# Sheet1.net
KiCad netlist of a schematic drawn in Altium Designer
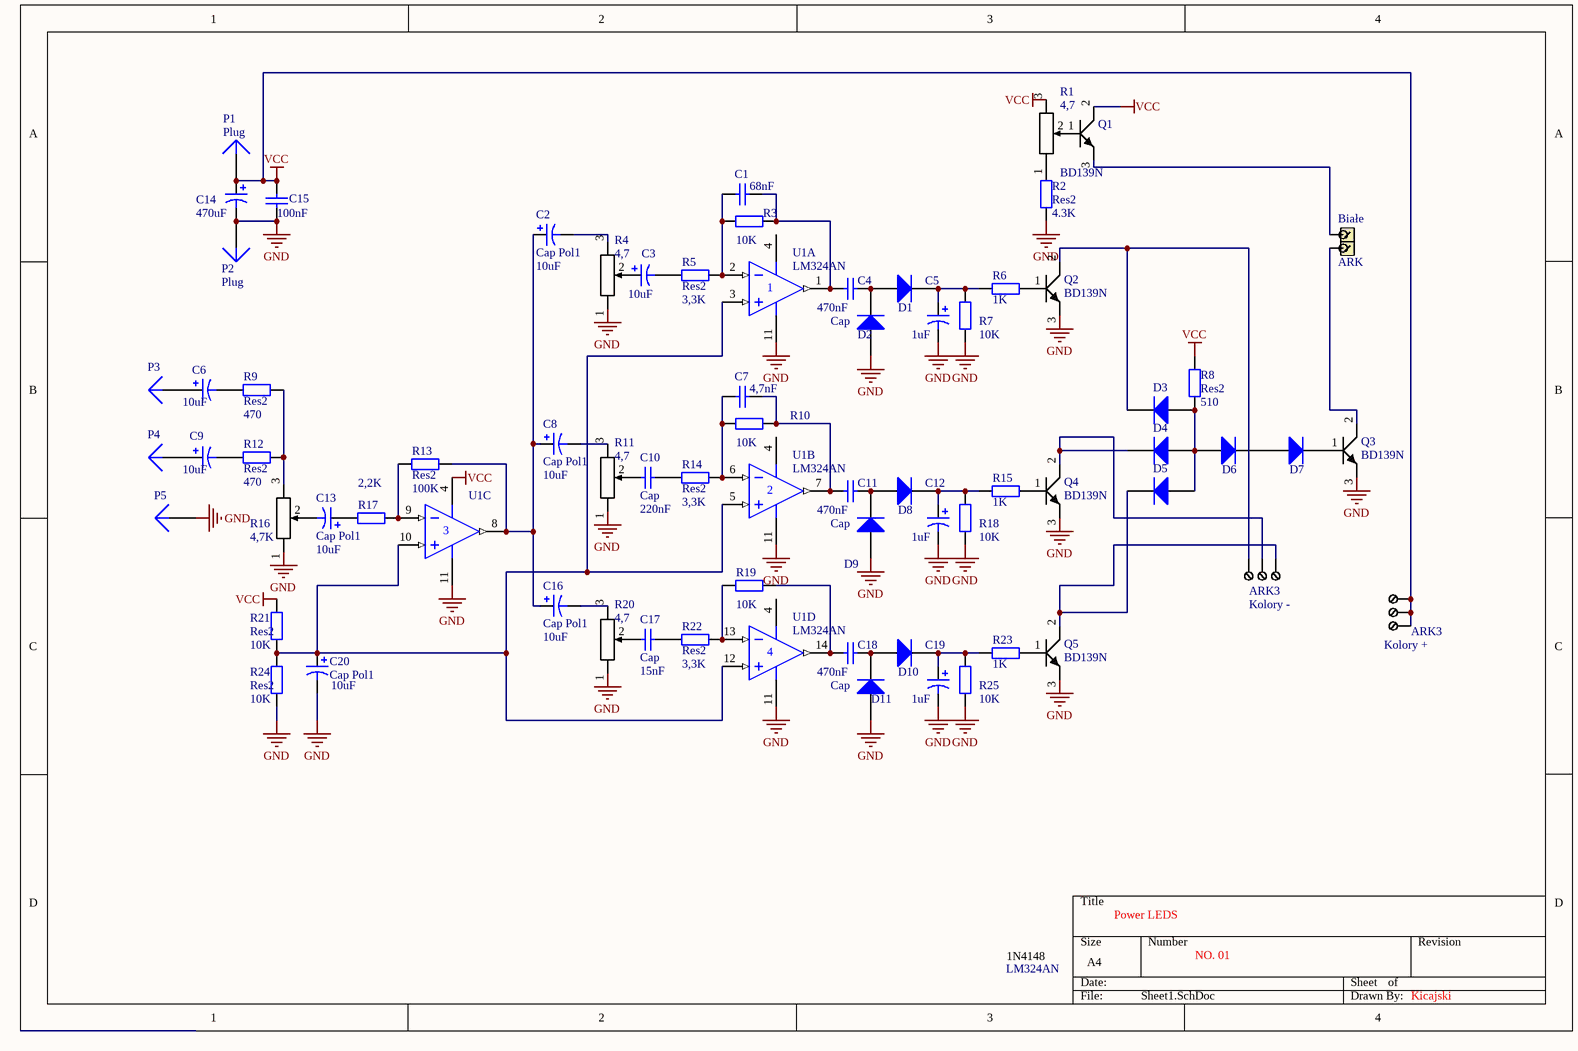
[diagram p0: Sheet1.SchDoc]

(export (version "E")
  (design (tool "Eeschema 10.0.6"))
  (components
    (comp (ref "Białe") (value "ARK") (footprint "ARK2") (libsource (lib "MOJASIM") (part "ARK")))
    (comp (ref "C1")
      (value "68nF")
      (footprint "RAD-0.2")
      (description "Capacitor")
      (fields (field (name "Comment") "Cap") (field (name "PUBLISHER") "Altium Limited"))
      (libsource (lib "Miscellaneous Devices") (part "Cap"))
    )
    (comp (ref "C2")
      (value "Cap Pol1")
      (footprint "CAPPR2.5-6.3x5")
      (description "Polarized Capacitor (Radial)")
      (fields (field (name "ALTIUM_VALUE") "10uF") (field (name "PUBLISHER") "Altium Limited"))
      (libsource (lib "Miscellaneous Devices") (part "Cap Pol1"))
    )
    (comp (ref "C3")
      (value "10uF")
      (footprint "CAPPR2.5-6.3x5")
      (description "Polarized Capacitor (Radial)")
      (fields (field (name "Comment") "Cap Pol1") (field (name "PUBLISHER") "Altium Limited"))
      (libsource (lib "Miscellaneous Devices") (part "Cap Pol1"))
    )
    (comp (ref "C4")
      (value "Cap")
      (footprint "RAD-0.2")
      (description "Capacitor")
      (fields (field (name "ALTIUM_VALUE") "470nF") (field (name "PUBLISHER") "Altium Limited"))
      (libsource (lib "Miscellaneous Devices") (part "Cap"))
    )
    (comp (ref "C5")
      (value "1uF")
      (footprint "CAPPR2.5-6.3x5")
      (description "Polarized Capacitor (Radial)")
      (fields (field (name "Comment") "Cap Pol1") (field (name "PUBLISHER") "Altium Limited"))
      (libsource (lib "Miscellaneous Devices") (part "Cap Pol1"))
    )
    (comp (ref "C6")
      (value "10uF")
      (footprint "CAPPR2.5-6.3x5")
      (description "Polarized Capacitor (Radial)")
      (fields (field (name "Comment") "Cap Pol1") (field (name "PUBLISHER") "Altium Limited"))
      (libsource (lib "Miscellaneous Devices") (part "Cap Pol1"))
    )
    (comp (ref "C7")
      (value "4,7nF")
      (footprint "RAD-0.2")
      (description "Capacitor")
      (fields (field (name "Comment") "Cap") (field (name "PUBLISHER") "Altium Limited"))
      (libsource (lib "Miscellaneous Devices") (part "Cap"))
    )
    (comp (ref "C8")
      (value "Cap Pol1")
      (footprint "CAPPR2.5-6.3x5")
      (description "Polarized Capacitor (Radial)")
      (fields (field (name "ALTIUM_VALUE") "10uF") (field (name "PUBLISHER") "Altium Limited"))
      (libsource (lib "Miscellaneous Devices") (part "Cap Pol1"))
    )
    (comp (ref "C9")
      (value "10uF")
      (footprint "CAPPR2.5-6.3x5")
      (description "Polarized Capacitor (Radial)")
      (fields (field (name "Comment") "Cap Pol1") (field (name "PUBLISHER") "Altium Limited"))
      (libsource (lib "Miscellaneous Devices") (part "Cap Pol1"))
    )
    (comp (ref "C10")
      (value "Cap")
      (footprint "RAD-0.2")
      (description "Capacitor")
      (fields (field (name "ALTIUM_VALUE") "220nF") (field (name "PUBLISHER") "Altium Limited"))
      (libsource (lib "Miscellaneous Devices") (part "Cap"))
    )
    (comp (ref "C11")
      (value "Cap")
      (footprint "RAD-0.2")
      (description "Capacitor")
      (fields (field (name "ALTIUM_VALUE") "470nF") (field (name "PUBLISHER") "Altium Limited"))
      (libsource (lib "Miscellaneous Devices") (part "Cap"))
    )
    (comp (ref "C12")
      (value "1uF")
      (footprint "CAPPR2.5-6.3x5")
      (description "Polarized Capacitor (Radial)")
      (fields (field (name "Comment") "Cap Pol1") (field (name "PUBLISHER") "Altium Limited"))
      (libsource (lib "Miscellaneous Devices") (part "Cap Pol1"))
    )
    (comp (ref "C13")
      (value "Cap Pol1")
      (footprint "CAPPR2.5-6.3x5")
      (description "Polarized Capacitor (Radial)")
      (fields (field (name "ALTIUM_VALUE") "10uF") (field (name "PUBLISHER") "Altium Limited"))
      (libsource (lib "Miscellaneous Devices") (part "Cap Pol1"))
    )
    (comp (ref "C14")
      (value "470uF")
      (footprint "CAPPR5-13x16")
      (description "Polarized Capacitor (Radial)")
      (fields (field (name "Comment") "Cap Pol1") (field (name "PUBLISHER") "Altium Limited"))
      (libsource (lib "Miscellaneous Devices") (part "Cap Pol1"))
    )
    (comp (ref "C15")
      (value "100nF")
      (footprint "RAD-0.3")
      (description "Capacitor")
      (fields (field (name "Comment") "Cap") (field (name "PUBLISHER") "Altium Limited"))
      (libsource (lib "Miscellaneous Devices") (part "Cap"))
    )
    (comp (ref "C16")
      (value "Cap Pol1")
      (footprint "CAPPR2.5-6.3x5")
      (description "Polarized Capacitor (Radial)")
      (fields (field (name "ALTIUM_VALUE") "10uF") (field (name "PUBLISHER") "Altium Limited"))
      (libsource (lib "Miscellaneous Devices") (part "Cap Pol1"))
    )
    (comp (ref "C17")
      (value "Cap")
      (footprint "RAD-0.2")
      (description "Capacitor")
      (fields (field (name "ALTIUM_VALUE") "15nF") (field (name "PUBLISHER") "Altium Limited"))
      (libsource (lib "Miscellaneous Devices") (part "Cap"))
    )
    (comp (ref "C18")
      (value "Cap")
      (footprint "RAD-0.2")
      (description "Capacitor")
      (fields (field (name "ALTIUM_VALUE") "470nF") (field (name "PUBLISHER") "Altium Limited"))
      (libsource (lib "Miscellaneous Devices") (part "Cap"))
    )
    (comp (ref "C19")
      (value "1uF")
      (footprint "CAPPR2.5-6.3x5")
      (description "Polarized Capacitor (Radial)")
      (fields (field (name "Comment") "Cap Pol1") (field (name "PUBLISHER") "Altium Limited"))
      (libsource (lib "Miscellaneous Devices") (part "Cap Pol1"))
    )
    (comp (ref "C20")
      (value "Cap Pol1")
      (footprint "CAPPR2.5-6.3x5")
      (description "Polarized Capacitor (Radial)")
      (fields (field (name "ALTIUM_VALUE") "10uF") (field (name "PUBLISHER") "Altium Limited"))
      (libsource (lib "Miscellaneous Devices") (part "Cap Pol1"))
    )
    (comp (ref "D1")
      (value "Diode 1N4148")
      (footprint "DO-35")
      (description "High Conductance Fast Diode")
      (fields (field (name "PUBLISHER") "Altium Limited"))
      (libsource (lib "Miscellaneous Devices") (part "Diode 1N4148"))
    )
    (comp (ref "D2")
      (value "Diode 1N4148")
      (footprint "DO-35")
      (description "High Conductance Fast Diode")
      (fields (field (name "PUBLISHER") "Altium Limited"))
      (libsource (lib "Miscellaneous Devices") (part "Diode 1N4148"))
    )
    (comp (ref "D3")
      (value "Diode 1N4148")
      (footprint "DO-35")
      (description "High Conductance Fast Diode")
      (fields (field (name "PUBLISHER") "Altium Limited"))
      (libsource (lib "Miscellaneous Devices") (part "Diode 1N4148"))
    )
    (comp (ref "D4")
      (value "Diode 1N4148")
      (footprint "DO-35")
      (description "High Conductance Fast Diode")
      (fields (field (name "PUBLISHER") "Altium Limited"))
      (libsource (lib "Miscellaneous Devices") (part "Diode 1N4148"))
    )
    (comp (ref "D5")
      (value "Diode 1N4148")
      (footprint "DO-35")
      (description "High Conductance Fast Diode")
      (fields (field (name "PUBLISHER") "Altium Limited"))
      (libsource (lib "Miscellaneous Devices") (part "Diode 1N4148"))
    )
    (comp (ref "D6")
      (value "Diode 1N4148")
      (footprint "DO-35")
      (description "High Conductance Fast Diode")
      (fields (field (name "PUBLISHER") "Altium Limited"))
      (libsource (lib "Miscellaneous Devices") (part "Diode 1N4148"))
    )
    (comp (ref "D7")
      (value "Diode 1N4148")
      (footprint "DO-35")
      (description "High Conductance Fast Diode")
      (fields (field (name "PUBLISHER") "Altium Limited"))
      (libsource (lib "Miscellaneous Devices") (part "Diode 1N4148"))
    )
    (comp (ref "D8")
      (value "Diode 1N4148")
      (footprint "DO-35")
      (description "High Conductance Fast Diode")
      (fields (field (name "PUBLISHER") "Altium Limited"))
      (libsource (lib "Miscellaneous Devices") (part "Diode 1N4148"))
    )
    (comp (ref "D9")
      (value "Diode 1N4148")
      (footprint "DO-35")
      (description "High Conductance Fast Diode")
      (fields (field (name "PUBLISHER") "Altium Limited"))
      (libsource (lib "Miscellaneous Devices") (part "Diode 1N4148"))
    )
    (comp (ref "D10")
      (value "Diode 1N4148")
      (footprint "DO-35")
      (description "High Conductance Fast Diode")
      (fields (field (name "PUBLISHER") "Altium Limited"))
      (libsource (lib "Miscellaneous Devices") (part "Diode 1N4148"))
    )
    (comp (ref "D11")
      (value "Diode 1N4148")
      (footprint "DO-35")
      (description "High Conductance Fast Diode")
      (fields (field (name "PUBLISHER") "Altium Limited"))
      (libsource (lib "Miscellaneous Devices") (part "Diode 1N4148"))
    )
    (comp (ref "Kolory +") (value "ARK3") (footprint "ARK3") (libsource (lib "MOJASIM") (part "ARK3")))
    (comp (ref "Kolory -") (value "ARK3") (footprint "ARK3") (libsource (lib "MOJASIM") (part "ARK3")))
    (comp (ref "P1")
      (value "Plug")
      (footprint "PIN1")
      (fields (field (name "PUBLISHER") "Altium Limited"))
      (libsource (lib "Miscellaneous Connectors") (part "Plug"))
    )
    (comp (ref "P2")
      (value "Plug")
      (footprint "PIN1")
      (fields (field (name "PUBLISHER") "Altium Limited"))
      (libsource (lib "Miscellaneous Connectors") (part "Plug"))
    )
    (comp (ref "P3")
      (value "Plug")
      (footprint "PIN1")
      (fields (field (name "PUBLISHER") "Altium Limited"))
      (libsource (lib "Miscellaneous Connectors") (part "Plug"))
    )
    (comp (ref "P4")
      (value "Plug")
      (footprint "PIN1")
      (fields (field (name "PUBLISHER") "Altium Limited"))
      (libsource (lib "Miscellaneous Connectors") (part "Plug"))
    )
    (comp (ref "P5")
      (value "Plug")
      (footprint "PIN1")
      (fields (field (name "PUBLISHER") "Altium Limited"))
      (libsource (lib "Miscellaneous Connectors") (part "Plug"))
    )
    (comp (ref "Q1") (value "BD139N") (footprint "BD139N") (libsource (lib "TQlibrary") (part "BD139N")))
    (comp (ref "Q2") (value "BD139N") (footprint "BD139N") (libsource (lib "TQlibrary") (part "BD139N")))
    (comp (ref "Q3") (value "BD139N") (footprint "BD139N") (libsource (lib "TQlibrary") (part "BD139N")))
    (comp (ref "Q4") (value "BD139N") (footprint "BD139N") (libsource (lib "TQlibrary") (part "BD139N")))
    (comp (ref "Q5") (value "BD139N") (footprint "BD139N") (libsource (lib "TQlibrary") (part "BD139N")))
    (comp (ref "R1")
      (value "4,7")
      (footprint "Potencjometr")
      (libsource (lib "TQlibrary") (part "Potencjometr"))
    )
    (comp (ref "R2")
      (value "Res2")
      (footprint "AXIAL-0.4")
      (description "Resistor")
      (fields (field (name "ALTIUM_VALUE") "4.3K") (field (name "PUBLISHER") "Altium Limited"))
      (libsource (lib "") (part "Res2_1"))
    )
    (comp (ref "R3")
      (value "10K")
      (footprint "AXIAL-0.4")
      (description "Resistor")
      (fields (field (name "Comment") "Res2") (field (name "PUBLISHER") "Altium Limited"))
      (libsource (lib "") (part "Res2_2"))
    )
    (comp (ref "R4")
      (value "4,7")
      (footprint "Potencjometr")
      (libsource (lib "TQlibrary") (part "Potencjometr"))
    )
    (comp (ref "R5")
      (value "Res2")
      (footprint "AXIAL-0.4")
      (description "Resistor")
      (fields (field (name "ALTIUM_VALUE") "3,3K") (field (name "PUBLISHER") "Altium Limited"))
      (libsource (lib "") (part "Res2_2"))
    )
    (comp (ref "R6")
      (value "1K")
      (footprint "AXIAL-0.4")
      (description "Resistor")
      (fields (field (name "Comment") "Res2") (field (name "PUBLISHER") "Altium Limited"))
      (libsource (lib "Miscellaneous Devices") (part "Res2"))
    )
    (comp (ref "R7")
      (value "10K")
      (footprint "AXIAL-0.4")
      (description "Resistor")
      (fields (field (name "Comment") "Res2") (field (name "PUBLISHER") "Altium Limited"))
      (libsource (lib "") (part "Res2_1"))
    )
    (comp (ref "R8")
      (value "Res2")
      (footprint "AXIAL-0.4")
      (description "Resistor")
      (fields (field (name "ALTIUM_VALUE") "510") (field (name "PUBLISHER") "Altium Limited"))
      (libsource (lib "") (part "Res2_1"))
    )
    (comp (ref "R9")
      (value "Res2")
      (footprint "AXIAL-0.4")
      (description "Resistor")
      (fields (field (name "ALTIUM_VALUE") "470") (field (name "PUBLISHER") "Altium Limited"))
      (libsource (lib "") (part "Res2_2"))
    )
    (comp (ref "R10")
      (value "10K")
      (footprint "AXIAL-0.4")
      (description "Resistor")
      (fields (field (name "Comment") "Res2") (field (name "PUBLISHER") "Altium Limited"))
      (libsource (lib "") (part "Res2_2"))
    )
    (comp (ref "R11")
      (value "4,7")
      (footprint "Potencjometr")
      (libsource (lib "TQlibrary") (part "Potencjometr"))
    )
    (comp (ref "R12")
      (value "Res2")
      (footprint "AXIAL-0.4")
      (description "Resistor")
      (fields (field (name "ALTIUM_VALUE") "470") (field (name "PUBLISHER") "Altium Limited"))
      (libsource (lib "") (part "Res2_2"))
    )
    (comp (ref "R13")
      (value "Res2")
      (footprint "AXIAL-0.4")
      (description "Resistor")
      (fields (field (name "ALTIUM_VALUE") "100K") (field (name "PUBLISHER") "Altium Limited"))
      (libsource (lib "") (part "Res2_2"))
    )
    (comp (ref "R14")
      (value "Res2")
      (footprint "AXIAL-0.4")
      (description "Resistor")
      (fields (field (name "ALTIUM_VALUE") "3,3K") (field (name "PUBLISHER") "Altium Limited"))
      (libsource (lib "") (part "Res2_2"))
    )
    (comp (ref "R15")
      (value "1K")
      (footprint "AXIAL-0.4")
      (description "Resistor")
      (fields (field (name "Comment") "Res2") (field (name "PUBLISHER") "Altium Limited"))
      (libsource (lib "Miscellaneous Devices") (part "Res2"))
    )
    (comp (ref "R16")
      (value "4,7K")
      (footprint "Potencjometr")
      (libsource (lib "TQlibrary") (part "Potencjometr"))
    )
    (comp (ref "R17")
      (value "2,2K")
      (footprint "AXIAL-0.4")
      (description "Resistor")
      (fields (field (name "Comment") "Res2") (field (name "PUBLISHER") "Altium Limited"))
      (libsource (lib "") (part "Res2_2"))
    )
    (comp (ref "R18")
      (value "10K")
      (footprint "AXIAL-0.4")
      (description "Resistor")
      (fields (field (name "Comment") "Res2") (field (name "PUBLISHER") "Altium Limited"))
      (libsource (lib "") (part "Res2_1"))
    )
    (comp (ref "R19")
      (value "10K")
      (footprint "AXIAL-0.4")
      (description "Resistor")
      (fields (field (name "Comment") "Res2") (field (name "PUBLISHER") "Altium Limited"))
      (libsource (lib "") (part "Res2_2"))
    )
    (comp (ref "R20")
      (value "4,7")
      (footprint "Potencjometr")
      (libsource (lib "TQlibrary") (part "Potencjometr"))
    )
    (comp (ref "R21")
      (value "Res2")
      (footprint "AXIAL-0.4")
      (description "Resistor")
      (fields (field (name "ALTIUM_VALUE") "10K") (field (name "PUBLISHER") "Altium Limited"))
      (libsource (lib "") (part "Res2_3"))
    )
    (comp (ref "R22")
      (value "Res2")
      (footprint "AXIAL-0.4")
      (description "Resistor")
      (fields (field (name "ALTIUM_VALUE") "3,3K") (field (name "PUBLISHER") "Altium Limited"))
      (libsource (lib "") (part "Res2_2"))
    )
    (comp (ref "R23")
      (value "1K")
      (footprint "AXIAL-0.4")
      (description "Resistor")
      (fields (field (name "Comment") "Res2") (field (name "PUBLISHER") "Altium Limited"))
      (libsource (lib "Miscellaneous Devices") (part "Res2"))
    )
    (comp (ref "R24")
      (value "Res2")
      (footprint "AXIAL-0.4")
      (description "Resistor")
      (fields (field (name "ALTIUM_VALUE") "10K") (field (name "PUBLISHER") "Altium Limited"))
      (libsource (lib "") (part "Res2_1"))
    )
    (comp (ref "R25")
      (value "10K")
      (footprint "AXIAL-0.4")
      (description "Resistor")
      (fields (field (name "Comment") "Res2") (field (name "PUBLISHER") "Altium Limited"))
      (libsource (lib "") (part "Res2_1"))
    )
    (comp (ref "U1")
      (value "LM324AN")
      (footprint "N014")
      (description "Quadruple Operational Amplifier")
      (fields (field (name "PUBLISHER") "Altium Limited"))
      (libsource (lib "TI Operational Amplifier") (part "LM324AN"))
    )
  )
  (nets
    (net (code "1") (name "GND") (class "Default")
      (node (ref "C12") (pin "2") (pinfunction "2_2") (pintype "passive"))
      (node (ref "C14") (pin "2") (pinfunction "2_2") (pintype "passive"))
      (node (ref "C15") (pin "1") (pinfunction "1_1") (pintype "passive"))
      (node (ref "C19") (pin "2") (pinfunction "2_2") (pintype "passive"))
      (node (ref "C20") (pin "2") (pinfunction "2_2") (pintype "passive"))
      (node (ref "C5") (pin "2") (pinfunction "2_2") (pintype "passive"))
      (node (ref "D11") (pin "1") (pinfunction "A_1") (pintype "passive"))
      (node (ref "D2") (pin "1") (pinfunction "A_1") (pintype "passive"))
      (node (ref "D9") (pin "1") (pinfunction "A_1") (pintype "passive"))
      (node (ref "P2") (pin "1") (pinfunction "1_1") (pintype "passive"))
      (node (ref "P5") (pin "1") (pinfunction "1_1") (pintype "passive"))
      (node (ref "Q2") (pin "3") (pinfunction "3_3") (pintype "passive"))
      (node (ref "Q3") (pin "3") (pinfunction "3_3") (pintype "passive"))
      (node (ref "Q4") (pin "3") (pinfunction "3_3") (pintype "passive"))
      (node (ref "Q5") (pin "3") (pinfunction "3_3") (pintype "passive"))
      (node (ref "R11") (pin "1") (pinfunction "1_1") (pintype "passive"))
      (node (ref "R16") (pin "1") (pinfunction "1_1") (pintype "passive"))
      (node (ref "R18") (pin "1") (pinfunction "1_1") (pintype "passive"))
      (node (ref "R2") (pin "1") (pinfunction "1_1") (pintype "passive"))
      (node (ref "R20") (pin "1") (pinfunction "1_1") (pintype "passive"))
      (node (ref "R24") (pin "1") (pinfunction "1_1") (pintype "passive"))
      (node (ref "R25") (pin "1") (pinfunction "1_1") (pintype "passive"))
      (node (ref "R4") (pin "1") (pinfunction "1_1") (pintype "passive"))
      (node (ref "R7") (pin "1") (pinfunction "1_1") (pintype "passive"))
      (node (ref "U1") (pin "11") (pinfunction "V-_11") (pintype "power_in"))
    )
    (net (code "2") (name "Net-(Białe-Pad1)") (class "Default")
      (node (ref "Białe") (pin "1") (pinfunction "1_1") (pintype "passive"))
      (node (ref "Q3") (pin "2") (pinfunction "2_2") (pintype "passive"))
    )
    (net (code "3") (name "Net-(Białe-Pad2)") (class "Default")
      (node (ref "Białe") (pin "2") (pinfunction "2_2") (pintype "passive"))
      (node (ref "Q1") (pin "3") (pinfunction "3_3") (pintype "passive"))
    )
    (net (code "4") (name "Net-(C2-Pad2)") (class "Default")
      (node (ref "C2") (pin "2") (pinfunction "2_2") (pintype "passive"))
      (node (ref "R4") (pin "3") (pinfunction "3_3") (pintype "passive"))
    )
    (net (code "5") (name "Net-(C3-Pad1)") (class "Default")
      (node (ref "C3") (pin "1") (pinfunction "1_1") (pintype "passive"))
      (node (ref "R4") (pin "2") (pinfunction "2_2") (pintype "passive"))
    )
    (net (code "6") (name "Net-(C3-Pad2)") (class "Default")
      (node (ref "C3") (pin "2") (pinfunction "2_2") (pintype "passive"))
      (node (ref "R5") (pin "1") (pinfunction "1_1") (pintype "passive"))
    )
    (net (code "7") (name "Net-(C6-Pad1)") (class "Default")
      (node (ref "C6") (pin "1") (pinfunction "1_1") (pintype "passive"))
      (node (ref "P3") (pin "1") (pinfunction "1_1") (pintype "passive"))
    )
    (net (code "8") (name "Net-(C6-Pad2)") (class "Default")
      (node (ref "C6") (pin "2") (pinfunction "2_2") (pintype "passive"))
      (node (ref "R9") (pin "1") (pinfunction "1_1") (pintype "passive"))
    )
    (net (code "9") (name "Net-(C8-Pad2)") (class "Default")
      (node (ref "C8") (pin "2") (pinfunction "2_2") (pintype "passive"))
      (node (ref "R11") (pin "3") (pinfunction "3_3") (pintype "passive"))
    )
    (net (code "10") (name "Net-(C9-Pad1)") (class "Default")
      (node (ref "C9") (pin "1") (pinfunction "1_1") (pintype "passive"))
      (node (ref "P4") (pin "1") (pinfunction "1_1") (pintype "passive"))
    )
    (net (code "11") (name "Net-(C9-Pad2)") (class "Default")
      (node (ref "C9") (pin "2") (pinfunction "2_2") (pintype "passive"))
      (node (ref "R12") (pin "1") (pinfunction "1_1") (pintype "passive"))
    )
    (net (code "12") (name "Net-(C10-Pad1)") (class "Default")
      (node (ref "C10") (pin "1") (pinfunction "1_1") (pintype "passive"))
      (node (ref "R11") (pin "2") (pinfunction "2_2") (pintype "passive"))
    )
    (net (code "13") (name "Net-(C10-Pad2)") (class "Default")
      (node (ref "C10") (pin "2") (pinfunction "2_2") (pintype "passive"))
      (node (ref "R14") (pin "1") (pinfunction "1_1") (pintype "passive"))
    )
    (net (code "14") (name "Net-(C13-Pad1)") (class "Default")
      (node (ref "C13") (pin "1") (pinfunction "1_1") (pintype "passive"))
      (node (ref "R17") (pin "1") (pinfunction "1_1") (pintype "passive"))
    )
    (net (code "15") (name "Net-(C13-Pad2)") (class "Default")
      (node (ref "C13") (pin "2") (pinfunction "2_2") (pintype "passive"))
      (node (ref "R16") (pin "2") (pinfunction "2_2") (pintype "passive"))
    )
    (net (code "16") (name "Net-(C16-Pad2)") (class "Default")
      (node (ref "C16") (pin "2") (pinfunction "2_2") (pintype "passive"))
      (node (ref "R20") (pin "3") (pinfunction "3_3") (pintype "passive"))
    )
    (net (code "17") (name "Net-(C17-Pad1)") (class "Default")
      (node (ref "C17") (pin "1") (pinfunction "1_1") (pintype "passive"))
      (node (ref "R20") (pin "2") (pinfunction "2_2") (pintype "passive"))
    )
    (net (code "18") (name "Net-(C17-Pad2)") (class "Default")
      (node (ref "C17") (pin "2") (pinfunction "2_2") (pintype "passive"))
      (node (ref "R22") (pin "1") (pinfunction "1_1") (pintype "passive"))
    )
    (net (code "19") (name "Net-(D1-A)") (class "Default")
      (node (ref "C4") (pin "2") (pinfunction "2_2") (pintype "passive"))
      (node (ref "D1") (pin "1") (pinfunction "A_1") (pintype "passive"))
      (node (ref "D2") (pin "2") (pinfunction "K_2") (pintype "passive"))
    )
    (net (code "20") (name "Net-(D1-K)") (class "Default")
      (node (ref "C5") (pin "1") (pinfunction "1_1") (pintype "passive"))
      (node (ref "D1") (pin "2") (pinfunction "K_2") (pintype "passive"))
      (node (ref "R6") (pin "2") (pinfunction "2_2") (pintype "passive"))
      (node (ref "R7") (pin "2") (pinfunction "2_2") (pintype "passive"))
    )
    (net (code "21") (name "Net-(D3-A)") (class "Default")
      (node (ref "D3") (pin "1") (pinfunction "A_1") (pintype "passive"))
      (node (ref "D4") (pin "1") (pinfunction "A_1") (pintype "passive"))
      (node (ref "D5") (pin "1") (pinfunction "A_1") (pintype "passive"))
      (node (ref "D6") (pin "1") (pinfunction "A_1") (pintype "passive"))
      (node (ref "R8") (pin "1") (pinfunction "1_1") (pintype "passive"))
    )
    (net (code "22") (name "Net-(D3-K)") (class "Default")
      (node (ref "D3") (pin "2") (pinfunction "K_2") (pintype "passive"))
      (node (ref "Kolory -") (pin "3") (pinfunction "3_3") (pintype "passive"))
      (node (ref "Q2") (pin "2") (pinfunction "2_2") (pintype "passive"))
    )
    (net (code "23") (name "Net-(D4-K)") (class "Default")
      (node (ref "D4") (pin "2") (pinfunction "K_2") (pintype "passive"))
      (node (ref "Kolory -") (pin "2") (pinfunction "2_2") (pintype "passive"))
      (node (ref "Q4") (pin "2") (pinfunction "2_2") (pintype "passive"))
    )
    (net (code "24") (name "Net-(D5-K)") (class "Default")
      (node (ref "D5") (pin "2") (pinfunction "K_2") (pintype "passive"))
      (node (ref "Kolory -") (pin "1") (pinfunction "1_1") (pintype "passive"))
      (node (ref "Q5") (pin "2") (pinfunction "2_2") (pintype "passive"))
    )
    (net (code "25") (name "Net-(D6-K)") (class "Default")
      (node (ref "D6") (pin "2") (pinfunction "K_2") (pintype "passive"))
      (node (ref "D7") (pin "1") (pinfunction "A_1") (pintype "passive"))
    )
    (net (code "26") (name "Net-(D7-K)") (class "Default")
      (node (ref "D7") (pin "2") (pinfunction "K_2") (pintype "passive"))
      (node (ref "Q3") (pin "1") (pinfunction "1_1") (pintype "passive"))
    )
    (net (code "27") (name "Net-(D8-A)") (class "Default")
      (node (ref "C11") (pin "2") (pinfunction "2_2") (pintype "passive"))
      (node (ref "D8") (pin "1") (pinfunction "A_1") (pintype "passive"))
      (node (ref "D9") (pin "2") (pinfunction "K_2") (pintype "passive"))
    )
    (net (code "28") (name "Net-(D8-K)") (class "Default")
      (node (ref "C12") (pin "1") (pinfunction "1_1") (pintype "passive"))
      (node (ref "D8") (pin "2") (pinfunction "K_2") (pintype "passive"))
      (node (ref "R15") (pin "2") (pinfunction "2_2") (pintype "passive"))
      (node (ref "R18") (pin "2") (pinfunction "2_2") (pintype "passive"))
    )
    (net (code "29") (name "Net-(D10-A)") (class "Default")
      (node (ref "C18") (pin "2") (pinfunction "2_2") (pintype "passive"))
      (node (ref "D10") (pin "1") (pinfunction "A_1") (pintype "passive"))
      (node (ref "D11") (pin "2") (pinfunction "K_2") (pintype "passive"))
    )
    (net (code "30") (name "Net-(D10-K)") (class "Default")
      (node (ref "C19") (pin "1") (pinfunction "1_1") (pintype "passive"))
      (node (ref "D10") (pin "2") (pinfunction "K_2") (pintype "passive"))
      (node (ref "R23") (pin "2") (pinfunction "2_2") (pintype "passive"))
      (node (ref "R25") (pin "2") (pinfunction "2_2") (pintype "passive"))
    )
    (net (code "31") (name "Net-(Q1-Pad1)") (class "Default")
      (node (ref "Q1") (pin "1") (pinfunction "1_1") (pintype "passive"))
      (node (ref "R1") (pin "2") (pinfunction "2_2") (pintype "passive"))
    )
    (net (code "32") (name "Net-(Q2-Pad1)") (class "Default")
      (node (ref "Q2") (pin "1") (pinfunction "1_1") (pintype "passive"))
      (node (ref "R6") (pin "1") (pinfunction "1_1") (pintype "passive"))
    )
    (net (code "33") (name "Net-(Q4-Pad1)") (class "Default")
      (node (ref "Q4") (pin "1") (pinfunction "1_1") (pintype "passive"))
      (node (ref "R15") (pin "1") (pinfunction "1_1") (pintype "passive"))
    )
    (net (code "34") (name "Net-(Q5-Pad1)") (class "Default")
      (node (ref "Q5") (pin "1") (pinfunction "1_1") (pintype "passive"))
      (node (ref "R23") (pin "1") (pinfunction "1_1") (pintype "passive"))
    )
    (net (code "35") (name "Net-(R1-Pad1)") (class "Default")
      (node (ref "R1") (pin "1") (pinfunction "1_1") (pintype "passive"))
      (node (ref "R2") (pin "2") (pinfunction "2_2") (pintype "passive"))
    )
    (net (code "36") (name "Net-(R12-Pad2)") (class "Default")
      (node (ref "R12") (pin "2") (pinfunction "2_2") (pintype "passive"))
      (node (ref "R16") (pin "3") (pinfunction "3_3") (pintype "passive"))
      (node (ref "R9") (pin "2") (pinfunction "2_2") (pintype "passive"))
    )
    (net (code "37") (name "Net-(U1A-IN+)") (class "Default")
      (node (ref "C20") (pin "1") (pinfunction "1_1") (pintype "passive"))
      (node (ref "R21") (pin "2") (pinfunction "2_2") (pintype "passive"))
      (node (ref "R24") (pin "2") (pinfunction "2_2") (pintype "passive"))
      (node (ref "U1") (pin "10") (pinfunction "IN+_10") (pintype "input"))
      (node (ref "U1") (pin "12") (pinfunction "IN+_12") (pintype "input"))
      (node (ref "U1") (pin "3") (pinfunction "IN+_3") (pintype "input"))
      (node (ref "U1") (pin "5") (pinfunction "IN+_5") (pintype "input"))
    )
    (net (code "38") (name "Net-(U1A-IN-)") (class "Default")
      (node (ref "C1") (pin "1") (pinfunction "1_1") (pintype "passive"))
      (node (ref "R3") (pin "1") (pinfunction "1_1") (pintype "passive"))
      (node (ref "R5") (pin "2") (pinfunction "2_2") (pintype "passive"))
      (node (ref "U1") (pin "2") (pinfunction "IN-_2") (pintype "input"))
    )
    (net (code "39") (name "Net-(U1A-OUT)") (class "Default")
      (node (ref "C1") (pin "2") (pinfunction "2_2") (pintype "passive"))
      (node (ref "C4") (pin "1") (pinfunction "1_1") (pintype "passive"))
      (node (ref "R3") (pin "2") (pinfunction "2_2") (pintype "passive"))
      (node (ref "U1") (pin "1") (pinfunction "OUT_1") (pintype "output"))
    )
    (net (code "40") (name "Net-(U1B-IN-)") (class "Default")
      (node (ref "C7") (pin "1") (pinfunction "1_1") (pintype "passive"))
      (node (ref "R10") (pin "1") (pinfunction "1_1") (pintype "passive"))
      (node (ref "R14") (pin "2") (pinfunction "2_2") (pintype "passive"))
      (node (ref "U1") (pin "6") (pinfunction "IN-_6") (pintype "input"))
    )
    (net (code "41") (name "Net-(U1B-OUT)") (class "Default")
      (node (ref "C11") (pin "1") (pinfunction "1_1") (pintype "passive"))
      (node (ref "C7") (pin "2") (pinfunction "2_2") (pintype "passive"))
      (node (ref "R10") (pin "2") (pinfunction "2_2") (pintype "passive"))
      (node (ref "U1") (pin "7") (pinfunction "OUT_7") (pintype "output"))
    )
    (net (code "42") (name "Net-(U1C-IN-)") (class "Default")
      (node (ref "R13") (pin "1") (pinfunction "1_1") (pintype "passive"))
      (node (ref "R17") (pin "2") (pinfunction "2_2") (pintype "passive"))
      (node (ref "U1") (pin "9") (pinfunction "IN-_9") (pintype "input"))
    )
    (net (code "43") (name "Net-(U1C-OUT)") (class "Default")
      (node (ref "C16") (pin "1") (pinfunction "1_1") (pintype "passive"))
      (node (ref "C2") (pin "1") (pinfunction "1_1") (pintype "passive"))
      (node (ref "C8") (pin "1") (pinfunction "1_1") (pintype "passive"))
      (node (ref "R13") (pin "2") (pinfunction "2_2") (pintype "passive"))
      (node (ref "U1") (pin "8") (pinfunction "OUT_8") (pintype "output"))
    )
    (net (code "44") (name "Net-(U1D-IN-)") (class "Default")
      (node (ref "R19") (pin "1") (pinfunction "1_1") (pintype "passive"))
      (node (ref "R22") (pin "2") (pinfunction "2_2") (pintype "passive"))
      (node (ref "U1") (pin "13") (pinfunction "IN-_13") (pintype "input"))
    )
    (net (code "45") (name "Net-(U1D-OUT)") (class "Default")
      (node (ref "C18") (pin "1") (pinfunction "1_1") (pintype "passive"))
      (node (ref "R19") (pin "2") (pinfunction "2_2") (pintype "passive"))
      (node (ref "U1") (pin "14") (pinfunction "OUT_14") (pintype "output"))
    )
    (net (code "46") (name "VCC") (class "Default")
      (node (ref "C14") (pin "1") (pinfunction "1_1") (pintype "passive"))
      (node (ref "C15") (pin "2") (pinfunction "2_2") (pintype "passive"))
      (node (ref "Kolory +") (pin "1") (pinfunction "1_1") (pintype "passive"))
      (node (ref "Kolory +") (pin "2") (pinfunction "2_2") (pintype "passive"))
      (node (ref "Kolory +") (pin "3") (pinfunction "3_3") (pintype "passive"))
      (node (ref "P1") (pin "1") (pinfunction "1_1") (pintype "passive"))
      (node (ref "Q1") (pin "2") (pinfunction "2_2") (pintype "passive"))
      (node (ref "R1") (pin "3") (pinfunction "3_3") (pintype "passive"))
      (node (ref "R21") (pin "1") (pinfunction "1_1") (pintype "passive"))
      (node (ref "R8") (pin "2") (pinfunction "2_2") (pintype "passive"))
      (node (ref "U1") (pin "4") (pinfunction "V+_4") (pintype "power_in"))
    )
    (net (code "47") (name "unconnected-(U1A-V+-Pad4)") (class "Default")
      (node (ref "U1") (pin "4") (pinfunction "V+_4") (pintype "power_in"))
    )
    (net (code "48") (name "unconnected-(U1B-V+-Pad4)") (class "Default")
      (node (ref "U1") (pin "4") (pinfunction "V+_4") (pintype "power_in"))
    )
    (net (code "49") (name "unconnected-(U1D-V+-Pad4)") (class "Default")
      (node (ref "U1") (pin "4") (pinfunction "V+_4") (pintype "power_in"))
    )
  )
)
